# BUCK_5v_TPS54340_P-MOS.net
KiCad netlist of a schematic drawn in Altium Designer
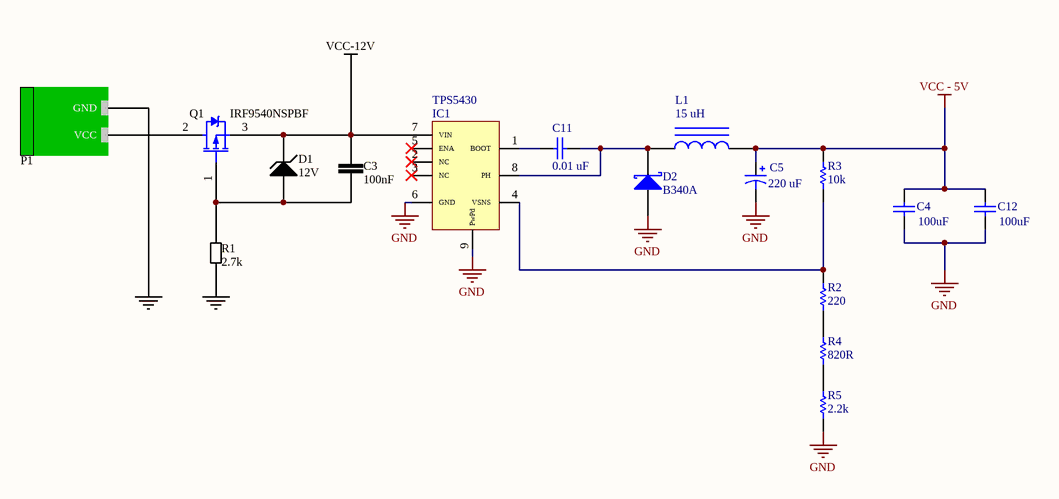
[diagram p0: BUCK_5v_TPS54340_P-MOS.SchDoc]

(export (version "E")
  (design (tool "Eeschema 10.0.6"))
  (components
    (comp (ref "C3")
      (value "100nF")
      (footprint "CER_0805")
      (description "CAP CER 100n 50V X7R 10% 0805")
      (libsource (lib "Capacitors") (part "00002105"))
    )
    (comp (ref "C4")
      (value "100uF")
      (footprint "RAD-0.3")
      (description "Capacitor")
      (fields (field (name "PUBLISHER") "Altium Limited"))
      (libsource (lib "Miscellaneous Devices") (part "Cap"))
    )
    (comp (ref "C5")
      (value "220 uF")
      (footprint "RB7.6-15")
      (description "Polarized Capacitor (Radial)")
      (fields (field (name "PUBLISHER") "Altium Limited"))
      (libsource (lib "Miscellaneous Devices") (part "Cap Pol1"))
    )
    (comp (ref "C11")
      (value "0.01 uF")
      (footprint "RAD-0.3")
      (description "Capacitor")
      (fields (field (name "PUBLISHER") "Altium Limited"))
      (libsource (lib "Miscellaneous Devices") (part "Cap"))
    )
    (comp (ref "C12")
      (value "100uF")
      (footprint "RAD-0.3")
      (description "Capacitor")
      (fields (field (name "PUBLISHER") "Altium Limited"))
      (libsource (lib "Miscellaneous Devices") (part "Cap"))
    )
    (comp (ref "D1")
      (value "12V")
      (footprint "DO214AC")
      (description "DIODE ZENER")
      (fields
        (field (name "MANUFACTURER") "Vishay Semiconductor Diodes Division")
        (field (name "MANUFACTURER PART NUMBER") "B360B")
      )
      (libsource (lib "Discrete_Semiconductor") (part "ZENER"))
    )
    (comp (ref "D2")
      (value "B340A")
      (footprint "SMB")
      (description "Schottky Diode")
      (fields (field (name "PUBLISHER") "Altium Limited"))
      (libsource (lib "Miscellaneous Devices") (part "D Schottky"))
    )
    (comp (ref "IC1")
      (value "TPS5430")
      (footprint "TPS5430")
      (libsource (lib "Schlib2_TPS5430") (part "TPS543?"))
    )
    (comp (ref "L1")
      (value "15 uH")
      (footprint "AXIAL-0.9")
      (description "Magnetic-Core Inductor")
      (fields (field (name "PUBLISHER") "Altium Limited"))
      (libsource (lib "Miscellaneous Devices") (part "Inductor Iron"))
    )
    (comp (ref "P1")
      (value "2EDGRC-5.08-02P-14-00A(H)")
      (footprint "PWR_Con")
      (description "TERM BLOCK HDR 2POS 90DEG 5.08MM")
      (libsource (lib "Electro_Mechanical") (part "00000002"))
    )
    (comp (ref "Q1")
      (value "IRF9540NSPBF")
      (footprint "D2PAK-2")
      (description "P-MOS")
      (fields (field (name "MANUFACTURER") "INTERNATIONAL RECTIFIER"))
      (libsource (lib "Discrete_Semiconductor") (part "IRF9540N"))
    )
    (comp (ref "R1")
      (value "2.7k")
      (footprint "RESC2013X38N-0805-NOOVERLAY")
      (description "RES SMD 2.7 kOhm 1/8W 0805")
      (fields (field (name "POWER") "0.125W, 1/8W"))
      (libsource (lib "Resistors") (part "00002701"))
    )
    (comp (ref "R2")
      (value "220")
      (footprint "AXIAL-0.3")
      (description "Resistor")
      (fields (field (name "PUBLISHER") "Altium Limited"))
      (libsource (lib "Miscellaneous Devices") (part "Res1"))
    )
    (comp (ref "R3")
      (value "10k")
      (footprint "AXIAL-0.3")
      (description "Resistor")
      (fields (field (name "PUBLISHER") "Altium Limited"))
      (libsource (lib "Miscellaneous Devices") (part "Res1"))
    )
    (comp (ref "R4")
      (value "820R")
      (footprint "AXIAL-0.3")
      (description "Resistor")
      (fields (field (name "PUBLISHER") "Altium Limited"))
      (libsource (lib "Miscellaneous Devices") (part "Res1"))
    )
    (comp (ref "R5")
      (value "2.2k")
      (footprint "AXIAL-0.3")
      (description "Resistor")
      (fields (field (name "PUBLISHER") "Altium Limited"))
      (libsource (lib "Miscellaneous Devices") (part "Res1"))
    )
  )
  (nets
    (net (code "1") (name "GND") (class "Default")
      (node (ref "C12") (pin "1") (pinfunction "1_1") (pintype "passive"))
      (node (ref "C4") (pin "1") (pinfunction "1_1") (pintype "passive"))
      (node (ref "C5") (pin "2") (pinfunction "2_2") (pintype "passive"))
      (node (ref "D2") (pin "1") (pinfunction "A_1") (pintype "passive"))
      (node (ref "IC1") (pin "6") (pinfunction "GND_6") (pintype "passive"))
      (node (ref "IC1") (pin "9") (pinfunction "PwPd_9") (pintype "passive"))
      (node (ref "P1") (pin "1") (pinfunction "GND_1") (pintype "passive"))
      (node (ref "R1") (pin "1") (pinfunction "1_1") (pintype "passive"))
      (node (ref "R5") (pin "1") (pinfunction "1_1") (pintype "passive"))
    )
    (net (code "2") (name "Net-(D1-Anode)") (class "Default")
      (node (ref "C3") (pin "1") (pinfunction "1_1") (pintype "passive"))
      (node (ref "D1") (pin "2") (pinfunction "Anode_2") (pintype "passive"))
      (node (ref "Q1") (pin "1") (pinfunction "G_1") (pintype "passive"))
      (node (ref "R1") (pin "2") (pinfunction "2_2") (pintype "passive"))
    )
    (net (code "3") (name "Net-(D2-K)") (class "Default")
      (node (ref "C11") (pin "2") (pinfunction "2_2") (pintype "passive"))
      (node (ref "D2") (pin "2") (pinfunction "K_2") (pintype "passive"))
      (node (ref "IC1") (pin "8") (pinfunction "PH_8") (pintype "passive"))
      (node (ref "L1") (pin "1") (pinfunction "1_1") (pintype "passive"))
    )
    (net (code "4") (name "Net-(IC1-BOOT)") (class "Default")
      (node (ref "C11") (pin "1") (pinfunction "1_1") (pintype "passive"))
      (node (ref "IC1") (pin "1") (pinfunction "BOOT_1") (pintype "passive"))
    )
    (net (code "5") (name "Net-(IC1-VSNS)") (class "Default")
      (node (ref "IC1") (pin "4") (pinfunction "VSNS_4") (pintype "passive"))
      (node (ref "R2") (pin "2") (pinfunction "2_2") (pintype "passive"))
      (node (ref "R3") (pin "1") (pinfunction "1_1") (pintype "passive"))
    )
    (net (code "6") (name "Net-(P1-VCC)") (class "Default")
      (node (ref "P1") (pin "2") (pinfunction "VCC_2") (pintype "passive"))
      (node (ref "Q1") (pin "2") (pinfunction "D_2") (pintype "passive"))
    )
    (net (code "7") (name "Net-(R2-Pad1)") (class "Default")
      (node (ref "R2") (pin "1") (pinfunction "1_1") (pintype "passive"))
      (node (ref "R4") (pin "2") (pinfunction "2_2") (pintype "passive"))
    )
    (net (code "8") (name "Net-(R4-Pad1)") (class "Default")
      (node (ref "R4") (pin "1") (pinfunction "1_1") (pintype "passive"))
      (node (ref "R5") (pin "2") (pinfunction "2_2") (pintype "passive"))
    )
    (net (code "9") (name "VCC - 5V") (class "Default")
      (node (ref "C12") (pin "2") (pinfunction "2_2") (pintype "passive"))
      (node (ref "C4") (pin "2") (pinfunction "2_2") (pintype "passive"))
      (node (ref "C5") (pin "1") (pinfunction "1_1") (pintype "passive"))
      (node (ref "L1") (pin "2") (pinfunction "2_2") (pintype "passive"))
      (node (ref "R3") (pin "2") (pinfunction "2_2") (pintype "passive"))
    )
    (net (code "10") (name "VCC-12V") (class "Default")
      (node (ref "C3") (pin "2") (pinfunction "2_2") (pintype "passive"))
      (node (ref "D1") (pin "1") (pinfunction "Cathode_1") (pintype "passive"))
      (node (ref "IC1") (pin "7") (pinfunction "VIN_7") (pintype "passive"))
      (node (ref "Q1") (pin "3") (pinfunction "S_3") (pintype "passive"))
    )
    (net (code "11") (name "unconnected-(IC1-ENA-Pad5)") (class "Default")
      (node (ref "IC1") (pin "5") (pinfunction "ENA_5") (pintype "passive+no_connect"))
    )
    (net (code "12") (name "unconnected-(IC1-NC-Pad2)") (class "Default")
      (node (ref "IC1") (pin "2") (pinfunction "NC_2") (pintype "passive+no_connect"))
    )
    (net (code "13") (name "unconnected-(IC1-NC-Pad3)") (class "Default")
      (node (ref "IC1") (pin "3") (pinfunction "NC_3") (pintype "passive+no_connect"))
    )
  )
)
